# QuadDeck.net
KiCad netlist of a schematic drawn in Altium Designer
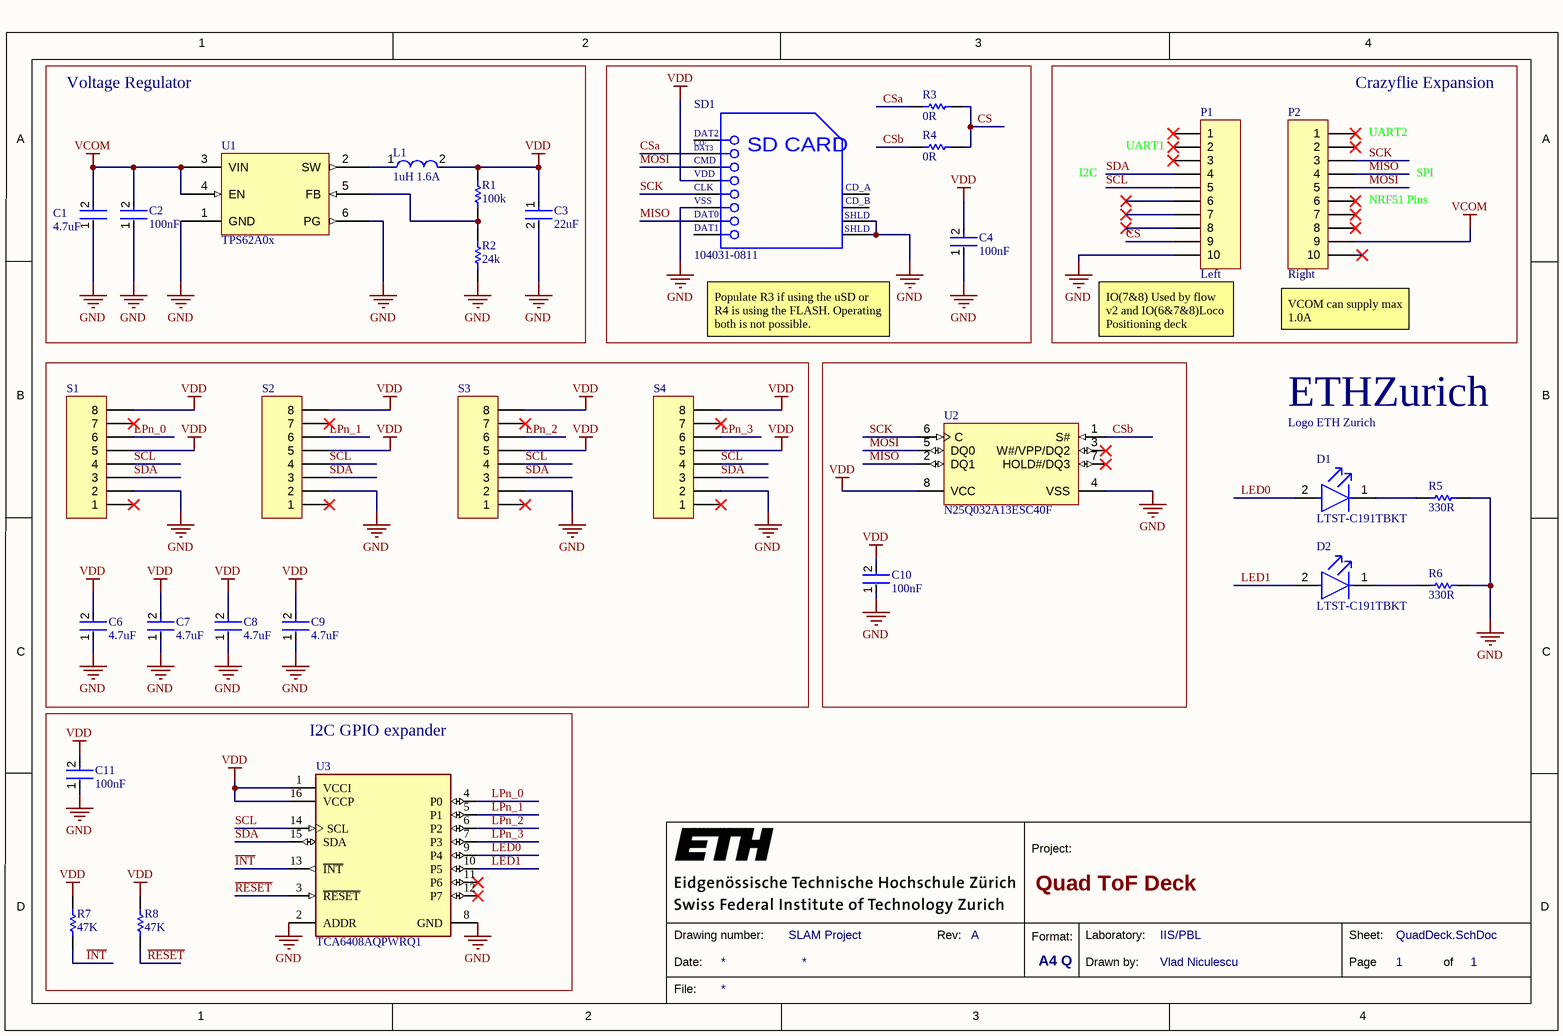
[diagram p0: QuadDeck.SchDoc]

(export (version "E")
  (design (tool "Eeschema 10.0.6"))
  (components
    (comp (ref "A1")
      (value "Logo ETH Zurich")
      (footprint "eth-zurich_3mm")
      (libsource (lib "Sensor_Node_Shield") (part "CMP-00038-1"))
    )
    (comp (ref "C1")
      (value "4.7uF")
      (footprint "FP-GRM188-0_1-MFG")
      (description "CAP CER 4.7UF 6.3V X5R 0603")
      (fields (field (name "VOLTAGE") "6.3V") (field (name "TOLERANCE") "10%"))
      (libsource (lib "Altium Content Vault") (part "236180d848d6139a670b325ea6854c9"))
    )
    (comp (ref "C2")
      (value "100nF")
      (footprint "FP-GRM15-MFG")
      (description "CAP CER 0.1UF 16V X7R 0402")
      (fields (field (name "MANUFACTURER PART NUMBER") "GRM155R71C104KA88D") (field (name "TOLERANCE") "10%"))
      (libsource (lib "Altium Content Vault") (part "236180d848d6139a670b325ea6854c9"))
    )
    (comp (ref "C3")
      (value "22uF")
      (footprint "FP-GRM21B-0_15-MFG")
      (description "Chip Multilayer Ceramic Capacitors for General Purpose, 0805, 22uF, X5R, 15%, 20%, 6.3V")
      (fields (field (name "VOLTAGE") "6.3V") (field (name "TOLERANCE") "20%"))
      (libsource (lib "Altium Content Vault") (part "b4654b650e69147ec39a6b967a45e02"))
    )
    (comp (ref "C4")
      (value "100nF")
      (footprint "FP-GRM15-MFG")
      (description "CAP CER 0.1UF 16V X7R 0402")
      (fields (field (name "MANUFACTURER PART NUMBER") "GRM155R71C104KA88D") (field (name "TOLERANCE") "10%"))
      (libsource (lib "Altium Content Vault") (part "236180d848d6139a670b325ea6854c9"))
    )
    (comp (ref "C6")
      (value "4.7uF")
      (footprint "FP-GRM188-0_1-MFG")
      (description "CAP CER 4.7UF 6.3V X5R 0603")
      (fields (field (name "VOLTAGE") "6.3V") (field (name "TOLERANCE") "10%"))
      (libsource (lib "Altium Content Vault") (part "236180d848d6139a670b325ea6854c9"))
    )
    (comp (ref "C7")
      (value "4.7uF")
      (footprint "FP-GRM188-0_1-MFG")
      (description "CAP CER 4.7UF 6.3V X5R 0603")
      (fields (field (name "VOLTAGE") "6.3V") (field (name "TOLERANCE") "10%"))
      (libsource (lib "Altium Content Vault") (part "236180d848d6139a670b325ea6854c9"))
    )
    (comp (ref "C8")
      (value "4.7uF")
      (footprint "FP-GRM188-0_1-MFG")
      (description "CAP CER 4.7UF 6.3V X5R 0603")
      (fields (field (name "VOLTAGE") "6.3V") (field (name "TOLERANCE") "10%"))
      (libsource (lib "Altium Content Vault") (part "236180d848d6139a670b325ea6854c9"))
    )
    (comp (ref "C9")
      (value "4.7uF")
      (footprint "FP-GRM188-0_1-MFG")
      (description "CAP CER 4.7UF 6.3V X5R 0603")
      (fields (field (name "VOLTAGE") "6.3V") (field (name "TOLERANCE") "10%"))
      (libsource (lib "Altium Content Vault") (part "236180d848d6139a670b325ea6854c9"))
    )
    (comp (ref "C10")
      (value "100nF")
      (footprint "FP-GRM15-MFG")
      (description "CAP CER 0.1UF 16V X7R 0402")
      (fields (field (name "MANUFACTURER PART NUMBER") "GRM155R71C104KA88D") (field (name "TOLERANCE") "10%"))
      (libsource (lib "Altium Content Vault") (part "236180d848d6139a670b325ea6854c9"))
    )
    (comp (ref "C11")
      (value "100nF")
      (footprint "FP-GRM15-MFG")
      (description "CAP CER 0.1UF 16V X7R 0402")
      (fields (field (name "MANUFACTURER PART NUMBER") "GRM155R71C104KA88D") (field (name "TOLERANCE") "10%"))
      (libsource (lib "Altium Content Vault") (part "236180d848d6139a670b325ea6854c9"))
    )
    (comp (ref "D1")
      (value "LTST-C191TBKT")
      (footprint "FP-LTST-C191TBKT-MFG")
      (description "LED BLUE CLEAR CHIP SMD")
      (libsource (lib "Altium Content Vault") (part "8706943c75ba83719d021d2fdc84c58"))
    )
    (comp (ref "D2")
      (value "LTST-C191TBKT")
      (footprint "FP-LTST-C191TBKT-MFG")
      (description "LED BLUE CLEAR CHIP SMD")
      (libsource (lib "Altium Content Vault") (part "8706943c75ba83719d021d2fdc84c58"))
    )
    (comp (ref "L1")
      (value "1uH 1.6A")
      (footprint "FP-LQM21PN_EH-w1_5-IPC_A")
      (description "FIXED IND 1UH 1.6A 107 MOHM SMD")
      (fields (field (name "TOLERANCE") "20%"))
      (libsource (lib "Altium Content Vault") (part "725321dda6339637d4d059423bc1c3c"))
    )
    (comp (ref "P1")
      (value "Left")
      (footprint "crazyflie-header:PCBComponent_1")
      (description "Header, 10-Pin")
      (fields (field (name "PUBLISHER") "Altium Limited"))
      (libsource (lib "Miscellaneous Connectors") (part "MHDR1X10"))
    )
    (comp (ref "P2")
      (value "Right")
      (footprint "crazyflie-header:PCBComponent_1")
      (description "Header, 10-Pin")
      (fields (field (name "PUBLISHER") "Altium Limited"))
      (libsource (lib "") (part "MHDR1X10_1"))
    )
    (comp (ref "R1")
      (value "100k")
      (footprint "RESC1608X55X30ML20T20")
      (fields (field (name "PART NUMBER") "ERA3AEB104V") (field (name "MANUFACTURER") "Panasonic"))
      (libsource (lib "Altium Content Vault") (part "RES"))
    )
    (comp (ref "R2")
      (value "24k")
      (footprint "RESC0603(1608)_N")
      (description "24K 0.1W 5% 0603 (1608 Metric)  SMD")
      (fields (field (name "TOLERANCE") "5 %") (field (name "POWER") "0.1 W"))
      (libsource (lib "Altium Content Vault") (part "RES"))
    )
    (comp (ref "R3")
      (value "0R")
      (footprint "RESC1005X40X25NL05T10")
      (fields (field (name "MANUFACTURER") "Yageo / Phycomp") (field (name "PART NUMBER") "RC0402JR-070RL"))
      (libsource (lib "Altium Content Vault") (part "RES"))
    )
    (comp (ref "R4")
      (value "0R")
      (footprint "RESC1005X40X25NL05T10")
      (fields (field (name "MANUFACTURER") "Yageo / Phycomp") (field (name "PART NUMBER") "RC0402JR-070RL"))
      (libsource (lib "Altium Content Vault") (part "RES"))
    )
    (comp (ref "R5")
      (value "330R")
      (footprint "RESC1608X55X25NL10T15")
      (description "Chip Resistor, 330 Ohm, +/- 1%, 0.1 W, -55 to 155 degC, 0603 (1608 Metric), RoHS, Tape and Reel")
      (fields (field (name "TOLERANCE") "10%"))
      (libsource (lib "Altium Content Vault") (part "RES-2"))
    )
    (comp (ref "R6")
      (value "330R")
      (footprint "RESC1608X55X25NL10T15")
      (description "Chip Resistor, 330 Ohm, +/- 1%, 0.1 W, -55 to 155 degC, 0603 (1608 Metric), RoHS, Tape and Reel")
      (fields (field (name "TOLERANCE") "10%"))
      (libsource (lib "Altium Content Vault") (part "RES-2"))
    )
    (comp (ref "R7")
      (value "47K")
      (footprint "RESC1608X55X30NL15T15")
      (description "Chip Resistor, 47 KOhm, +/- 1%, 0.1 W, -55 to 155 degC, 0603 (1608 Metric), RoHS, Tape and Reel")
      (libsource (lib "Altium Content Vault") (part "RES-2"))
    )
    (comp (ref "R8")
      (value "47K")
      (footprint "RESC1608X55X30NL15T15")
      (description "Chip Resistor, 47 KOhm, +/- 1%, 0.1 W, -55 to 155 degC, 0603 (1608 Metric), RoHS, Tape and Reel")
      (libsource (lib "Altium Content Vault") (part "RES-2"))
    )
    (comp (ref "S1")
      (value "Header")
      (footprint "tof-connector")
      (description "Header, 8-Pin")
      (fields (field (name "PUBLISHER") "Altium Limited"))
      (libsource (lib "Miscellaneous Connectors") (part "Header 8"))
    )
    (comp (ref "S2")
      (value "Header")
      (footprint "tof-connector")
      (description "Header, 8-Pin")
      (fields (field (name "PUBLISHER") "Altium Limited"))
      (libsource (lib "Miscellaneous Connectors") (part "Header 8"))
    )
    (comp (ref "S3")
      (value "Header")
      (footprint "tof-connector")
      (description "Header, 8-Pin")
      (fields (field (name "PUBLISHER") "Altium Limited"))
      (libsource (lib "Miscellaneous Connectors") (part "Header 8"))
    )
    (comp (ref "S4")
      (value "Header")
      (footprint "tof-connector")
      (description "Header, 8-Pin")
      (fields (field (name "PUBLISHER") "Altium Limited"))
      (libsource (lib "Miscellaneous Connectors") (part "Header 8"))
    )
    (comp (ref "SD1")
      (value "104031-0811")
      (footprint "MOLX-104031-0811_V")
      (description "Micro SD Card, RA, -25 to 85 degC, 8-Pin SMD, RoHS, Tape and Reel")
      (fields (field (name "MANUFACTURER") "Molex"))
      (libsource (lib "Altium Content Vault") (part "CN-SD-8-2SW-2S"))
    )
    (comp (ref "U1")
      (value "TPS62A0x")
      (footprint "SOT50P245X110-6N")
      (libsource (lib "TPS62A01") (part "TPS62A01"))
    )
    (comp (ref "U2")
      (value "N25Q032A13ESC40F")
      (footprint "MICT-SC-8_N")
      (fields (field (name "MANUFACTURER") "Micron") (field (name "VOLTAGE") "2.7V-3.6VÂ"))
      (libsource (lib "Altium Content Vault") (part "MICT-N25Q032SC-8"))
    )
    (comp (ref "U3")
      (value "TCA6408AQPWRQ1")
      (footprint "FP-PW0016A-IPC_B")
      (description "IC I/O EXPANDER I2C 8B 16TSSOP")
      (libsource (lib "Altium Content Vault") (part "945f262353ccef2f090be9ef51e4a3e"))
    )
  )
  (nets
    (net (code "1") (name "/CS") (class "Default")
      (node (ref "P1") (pin "9") (pinfunction "9_9") (pintype "passive"))
      (node (ref "R3") (pin "2") (pinfunction "2_2") (pintype "passive"))
      (node (ref "R4") (pin "2") (pinfunction "2_2") (pintype "passive"))
    )
    (net (code "2") (name "/CSa") (class "Default")
      (node (ref "R3") (pin "1") (pinfunction "1_1") (pintype "passive"))
      (node (ref "SD1") (pin "2") (pinfunction "CMD_2") (pintype "passive"))
    )
    (net (code "3") (name "/CSb") (class "Default")
      (node (ref "R4") (pin "1") (pinfunction "1_1") (pintype "passive"))
      (node (ref "U2") (pin "1") (pinfunction "S#_1") (pintype "input"))
    )
    (net (code "4") (name "/INT") (class "Default")
      (node (ref "R7") (pin "1") (pinfunction "1_1") (pintype "passive"))
      (node (ref "U3") (pin "13") (pinfunction "~{INT}_13") (pintype "output"))
    )
    (net (code "5") (name "/LED0") (class "Default")
      (node (ref "D1") (pin "2") (pinfunction "A_2") (pintype "passive"))
      (node (ref "U3") (pin "9") (pinfunction "P4_9") (pintype "bidirectional"))
    )
    (net (code "6") (name "/LED1") (class "Default")
      (node (ref "D2") (pin "2") (pinfunction "A_2") (pintype "passive"))
      (node (ref "U3") (pin "10") (pinfunction "P5_10") (pintype "bidirectional"))
    )
    (net (code "7") (name "/LPn_0") (class "Default")
      (node (ref "S1") (pin "6") (pinfunction "6_6") (pintype "passive"))
      (node (ref "U3") (pin "4") (pinfunction "P0_4") (pintype "bidirectional"))
    )
    (net (code "8") (name "/LPn_1") (class "Default")
      (node (ref "S2") (pin "6") (pinfunction "6_6") (pintype "passive"))
      (node (ref "U3") (pin "5") (pinfunction "P1_5") (pintype "bidirectional"))
    )
    (net (code "9") (name "/LPn_2") (class "Default")
      (node (ref "S3") (pin "6") (pinfunction "6_6") (pintype "passive"))
      (node (ref "U3") (pin "6") (pinfunction "P2_6") (pintype "bidirectional"))
    )
    (net (code "10") (name "/LPn_3") (class "Default")
      (node (ref "S4") (pin "6") (pinfunction "6_6") (pintype "passive"))
      (node (ref "U3") (pin "7") (pinfunction "P3_7") (pintype "bidirectional"))
    )
    (net (code "11") (name "/MISO") (class "Default")
      (node (ref "P2") (pin "4") (pinfunction "4_4") (pintype "passive"))
      (node (ref "SD1") (pin "7") (pinfunction "DAT0_7") (pintype "passive"))
      (node (ref "U2") (pin "2") (pinfunction "DQ1_2") (pintype "bidirectional"))
    )
    (net (code "12") (name "/MOSI") (class "Default")
      (node (ref "P2") (pin "5") (pinfunction "5_5") (pintype "passive"))
      (node (ref "SD1") (pin "3") (pinfunction "VSS1_3") (pintype "passive"))
      (node (ref "U2") (pin "5") (pinfunction "DQ0_5") (pintype "bidirectional"))
    )
    (net (code "13") (name "/RESET") (class "Default")
      (node (ref "R8") (pin "1") (pinfunction "1_1") (pintype "passive"))
      (node (ref "U3") (pin "3") (pinfunction "~{RESET}_3") (pintype "input"))
    )
    (net (code "14") (name "/SCK") (class "Default")
      (node (ref "P2") (pin "3") (pinfunction "3_3") (pintype "passive"))
      (node (ref "SD1") (pin "5") (pinfunction "CLK_5") (pintype "passive"))
      (node (ref "U2") (pin "6") (pinfunction "C_6") (pintype "input"))
    )
    (net (code "15") (name "/SCL") (class "Default")
      (node (ref "P1") (pin "5") (pinfunction "5_5") (pintype "passive"))
      (node (ref "S1") (pin "4") (pinfunction "4_4") (pintype "passive"))
      (node (ref "S2") (pin "4") (pinfunction "4_4") (pintype "passive"))
      (node (ref "S3") (pin "4") (pinfunction "4_4") (pintype "passive"))
      (node (ref "S4") (pin "4") (pinfunction "4_4") (pintype "passive"))
      (node (ref "U3") (pin "14") (pinfunction "SCL_14") (pintype "input"))
    )
    (net (code "16") (name "/SDA") (class "Default")
      (node (ref "P1") (pin "4") (pinfunction "4_4") (pintype "passive"))
      (node (ref "S1") (pin "3") (pinfunction "3_3") (pintype "passive"))
      (node (ref "S2") (pin "3") (pinfunction "3_3") (pintype "passive"))
      (node (ref "S3") (pin "3") (pinfunction "3_3") (pintype "passive"))
      (node (ref "S4") (pin "3") (pinfunction "3_3") (pintype "passive"))
      (node (ref "U3") (pin "15") (pinfunction "SDA_15") (pintype "bidirectional"))
    )
    (net (code "17") (name "GND") (class "Default")
      (node (ref "C1") (pin "1") (pinfunction "1_1") (pintype "passive"))
      (node (ref "C10") (pin "1") (pinfunction "1_1") (pintype "passive"))
      (node (ref "C11") (pin "1") (pinfunction "1_1") (pintype "passive"))
      (node (ref "C2") (pin "1") (pinfunction "1_1") (pintype "passive"))
      (node (ref "C3") (pin "2") (pinfunction "2_2") (pintype "passive"))
      (node (ref "C4") (pin "1") (pinfunction "1_1") (pintype "passive"))
      (node (ref "C6") (pin "1") (pinfunction "1_1") (pintype "passive"))
      (node (ref "C7") (pin "1") (pinfunction "1_1") (pintype "passive"))
      (node (ref "C8") (pin "1") (pinfunction "1_1") (pintype "passive"))
      (node (ref "C9") (pin "1") (pinfunction "1_1") (pintype "passive"))
      (node (ref "P1") (pin "10") (pinfunction "10_10") (pintype "passive"))
      (node (ref "R2") (pin "1") (pinfunction "1_1") (pintype "passive"))
      (node (ref "R5") (pin "2") (pinfunction "2_2") (pintype "passive"))
      (node (ref "R6") (pin "2") (pinfunction "2_2") (pintype "passive"))
      (node (ref "S1") (pin "2") (pinfunction "2_2") (pintype "passive"))
      (node (ref "S2") (pin "2") (pinfunction "2_2") (pintype "passive"))
      (node (ref "S3") (pin "2") (pinfunction "2_2") (pintype "passive"))
      (node (ref "S4") (pin "2") (pinfunction "2_2") (pintype "passive"))
      (node (ref "SD1") (pin "11") (pinfunction "SHLD1_11") (pintype "passive"))
      (node (ref "SD1") (pin "12") (pinfunction "SHLD2_12") (pintype "passive"))
      (node (ref "SD1") (pin "6") (pinfunction "VSS2_6") (pintype "passive"))
      (node (ref "U1") (pin "1") (pinfunction "GND_1") (pintype "passive"))
      (node (ref "U1") (pin "6") (pinfunction "PG_6") (pintype "output"))
      (node (ref "U2") (pin "4") (pinfunction "VSS_4") (pintype "power_in"))
      (node (ref "U3") (pin "2") (pinfunction "ADDR_2") (pintype "power_in"))
      (node (ref "U3") (pin "8") (pinfunction "GND_8") (pintype "power_in"))
    )
    (net (code "18") (name "Net-(D1-C)") (class "Default")
      (node (ref "D1") (pin "1") (pinfunction "C_1") (pintype "passive"))
      (node (ref "R5") (pin "1") (pinfunction "1_1") (pintype "passive"))
    )
    (net (code "19") (name "Net-(D2-C)") (class "Default")
      (node (ref "D2") (pin "1") (pinfunction "C_1") (pintype "passive"))
      (node (ref "R6") (pin "1") (pinfunction "1_1") (pintype "passive"))
    )
    (net (code "20") (name "Net-(U1-FB)") (class "Default")
      (node (ref "R1") (pin "1") (pinfunction "1_1") (pintype "passive"))
      (node (ref "R2") (pin "2") (pinfunction "2_2") (pintype "passive"))
      (node (ref "U1") (pin "5") (pinfunction "FB_5") (pintype "input"))
    )
    (net (code "21") (name "Net-(U1-SW)") (class "Default")
      (node (ref "L1") (pin "1") (pinfunction "1_1") (pintype "passive"))
      (node (ref "U1") (pin "2") (pinfunction "SW_2") (pintype "output"))
    )
    (net (code "22") (name "VCOM") (class "Default")
      (node (ref "C1") (pin "2") (pinfunction "2_2") (pintype "passive"))
      (node (ref "C2") (pin "2") (pinfunction "2_2") (pintype "passive"))
      (node (ref "P2") (pin "9") (pinfunction "9_9") (pintype "passive"))
      (node (ref "U1") (pin "3") (pinfunction "VIN_3") (pintype "power_in"))
      (node (ref "U1") (pin "4") (pinfunction "EN_4") (pintype "input"))
    )
    (net (code "23") (name "VDD") (class "Default")
      (node (ref "C10") (pin "2") (pinfunction "2_2") (pintype "passive"))
      (node (ref "C11") (pin "2") (pinfunction "2_2") (pintype "passive"))
      (node (ref "C3") (pin "1") (pinfunction "1_1") (pintype "passive"))
      (node (ref "C4") (pin "2") (pinfunction "2_2") (pintype "passive"))
      (node (ref "C6") (pin "2") (pinfunction "2_2") (pintype "passive"))
      (node (ref "C7") (pin "2") (pinfunction "2_2") (pintype "passive"))
      (node (ref "C8") (pin "2") (pinfunction "2_2") (pintype "passive"))
      (node (ref "C9") (pin "2") (pinfunction "2_2") (pintype "passive"))
      (node (ref "L1") (pin "2") (pinfunction "2_2") (pintype "passive"))
      (node (ref "R1") (pin "2") (pinfunction "2_2") (pintype "passive"))
      (node (ref "R7") (pin "2") (pinfunction "2_2") (pintype "passive"))
      (node (ref "R8") (pin "2") (pinfunction "2_2") (pintype "passive"))
      (node (ref "S1") (pin "5") (pinfunction "5_5") (pintype "passive"))
      (node (ref "S1") (pin "8") (pinfunction "8_8") (pintype "passive"))
      (node (ref "S2") (pin "5") (pinfunction "5_5") (pintype "passive"))
      (node (ref "S2") (pin "8") (pinfunction "8_8") (pintype "passive"))
      (node (ref "S3") (pin "5") (pinfunction "5_5") (pintype "passive"))
      (node (ref "S3") (pin "8") (pinfunction "8_8") (pintype "passive"))
      (node (ref "S4") (pin "5") (pinfunction "5_5") (pintype "passive"))
      (node (ref "S4") (pin "8") (pinfunction "8_8") (pintype "passive"))
      (node (ref "SD1") (pin "4") (pinfunction "VDD_4") (pintype "passive"))
      (node (ref "U2") (pin "8") (pinfunction "VCC_8") (pintype "power_in"))
      (node (ref "U3") (pin "1") (pinfunction "VCCI_1") (pintype "power_in"))
      (node (ref "U3") (pin "16") (pinfunction "VCCP_16") (pintype "power_in"))
    )
    (net (code "24") (name "unconnected-(P1-Pad1)") (class "Default")
      (node (ref "P1") (pin "1") (pinfunction "1_1") (pintype "passive+no_connect"))
    )
    (net (code "25") (name "unconnected-(P1-Pad2)") (class "Default")
      (node (ref "P1") (pin "2") (pinfunction "2_2") (pintype "passive+no_connect"))
    )
    (net (code "26") (name "unconnected-(P1-Pad3)") (class "Default")
      (node (ref "P1") (pin "3") (pinfunction "3_3") (pintype "passive+no_connect"))
    )
    (net (code "27") (name "unconnected-(P1-Pad6)") (class "Default")
      (node (ref "P1") (pin "6") (pinfunction "6_6") (pintype "passive+no_connect"))
    )
    (net (code "28") (name "unconnected-(P1-Pad7)") (class "Default")
      (node (ref "P1") (pin "7") (pinfunction "7_7") (pintype "passive+no_connect"))
    )
    (net (code "29") (name "unconnected-(P1-Pad8)") (class "Default")
      (node (ref "P1") (pin "8") (pinfunction "8_8") (pintype "passive+no_connect"))
    )
    (net (code "30") (name "unconnected-(P2-Pad1)") (class "Default")
      (node (ref "P2") (pin "1") (pinfunction "1_1") (pintype "passive+no_connect"))
    )
    (net (code "31") (name "unconnected-(P2-Pad2)") (class "Default")
      (node (ref "P2") (pin "2") (pinfunction "2_2") (pintype "passive+no_connect"))
    )
    (net (code "32") (name "unconnected-(P2-Pad6)") (class "Default")
      (node (ref "P2") (pin "6") (pinfunction "6_6") (pintype "passive+no_connect"))
    )
    (net (code "33") (name "unconnected-(P2-Pad7)") (class "Default")
      (node (ref "P2") (pin "7") (pinfunction "7_7") (pintype "passive+no_connect"))
    )
    (net (code "34") (name "unconnected-(P2-Pad8)") (class "Default")
      (node (ref "P2") (pin "8") (pinfunction "8_8") (pintype "passive+no_connect"))
    )
    (net (code "35") (name "unconnected-(P2-Pad10)") (class "Default")
      (node (ref "P2") (pin "10") (pinfunction "10_10") (pintype "passive+no_connect"))
    )
    (net (code "36") (name "unconnected-(S1-Pad1)") (class "Default")
      (node (ref "S1") (pin "1") (pinfunction "1_1") (pintype "passive+no_connect"))
    )
    (net (code "37") (name "unconnected-(S1-Pad7)") (class "Default")
      (node (ref "S1") (pin "7") (pinfunction "7_7") (pintype "passive+no_connect"))
    )
    (net (code "38") (name "unconnected-(S2-Pad1)") (class "Default")
      (node (ref "S2") (pin "1") (pinfunction "1_1") (pintype "passive+no_connect"))
    )
    (net (code "39") (name "unconnected-(S2-Pad7)") (class "Default")
      (node (ref "S2") (pin "7") (pinfunction "7_7") (pintype "passive+no_connect"))
    )
    (net (code "40") (name "unconnected-(S3-Pad1)") (class "Default")
      (node (ref "S3") (pin "1") (pinfunction "1_1") (pintype "passive+no_connect"))
    )
    (net (code "41") (name "unconnected-(S3-Pad7)") (class "Default")
      (node (ref "S3") (pin "7") (pinfunction "7_7") (pintype "passive+no_connect"))
    )
    (net (code "42") (name "unconnected-(S4-Pad1)") (class "Default")
      (node (ref "S4") (pin "1") (pinfunction "1_1") (pintype "passive+no_connect"))
    )
    (net (code "43") (name "unconnected-(S4-Pad7)") (class "Default")
      (node (ref "S4") (pin "7") (pinfunction "7_7") (pintype "passive+no_connect"))
    )
    (net (code "44") (name "unconnected-(SD1-CD_A-Pad9)") (class "Default")
      (node (ref "SD1") (pin "9") (pinfunction "CD_A_9") (pintype "passive"))
    )
    (net (code "45") (name "unconnected-(SD1-CD_B-Pad10)") (class "Default")
      (node (ref "SD1") (pin "10") (pinfunction "CD_B_10") (pintype "passive"))
    )
    (net (code "46") (name "unconnected-(SD1-CD{slash}DAT3-Pad1)") (class "Default")
      (node (ref "SD1") (pin "1") (pinfunction "CD/DAT3_1") (pintype "passive"))
    )
    (net (code "47") (name "unconnected-(SD1-DAT1-Pad8)") (class "Default")
      (node (ref "SD1") (pin "8") (pinfunction "DAT1_8") (pintype "passive"))
    )
    (net (code "48") (name "unconnected-(U2-HOLD#{slash}DQ3-Pad7)") (class "Default")
      (node (ref "U2") (pin "7") (pinfunction "HOLD#/DQ3_7") (pintype "bidirectional+no_connect"))
    )
    (net (code "49") (name "unconnected-(U2-W#{slash}VPP{slash}DQ2-Pad3)") (class "Default")
      (node (ref "U2") (pin "3") (pinfunction "W#/VPP/DQ2_3") (pintype "bidirectional+no_connect"))
    )
    (net (code "50") (name "unconnected-(U3-P6-Pad11)") (class "Default")
      (node (ref "U3") (pin "11") (pinfunction "P6_11") (pintype "bidirectional+no_connect"))
    )
    (net (code "51") (name "unconnected-(U3-P7-Pad12)") (class "Default")
      (node (ref "U3") (pin "12") (pinfunction "P7_12") (pintype "bidirectional+no_connect"))
    )
  )
)
